# 8_Airframe-Misc.net
KiCad netlist of a schematic drawn in Altium Designer
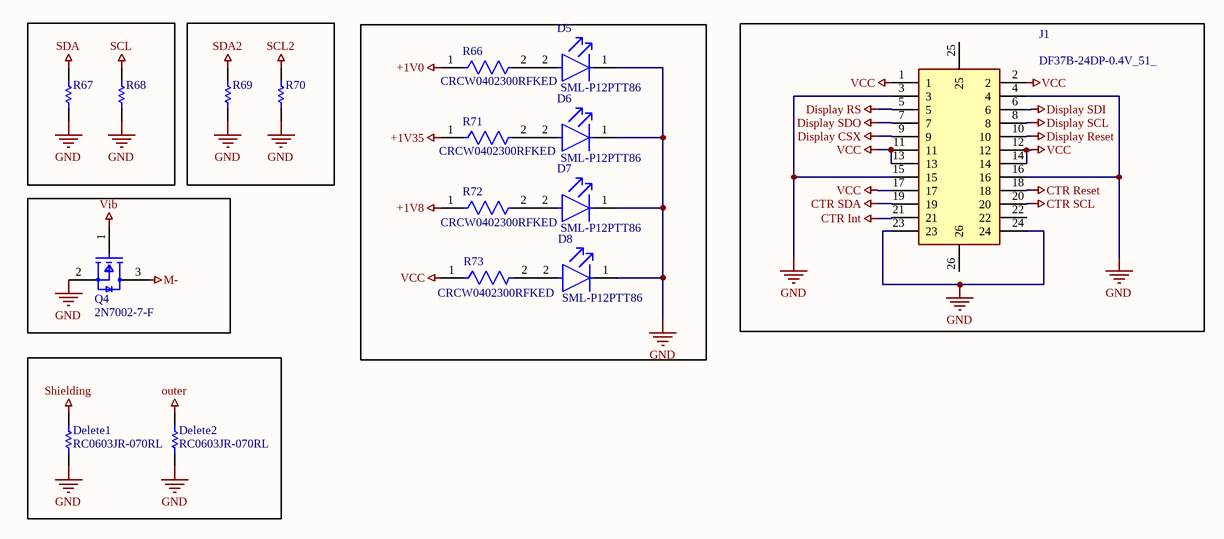
[diagram p0: 8_Airframe-Misc.SchDoc]

(export (version "E")
  (design (tool "Eeschema 10.0.6"))
  (components
    (comp (ref "D5")
      (value "SML-P12PTT86")
      (footprint "FP-SML-P1-MFG")
      (description "LED GREEN CLEAR 1006 SMD")
      (fields
        (field (name "MANUFACTURER") "Rohm")
        (field (name "OCTOPART") "https://octopart.com/sml-p12ptt86-rohm-9290705")
      )
      (libsource (lib "Altium Content Vault") (part "8706943c75ba83719d021d2fdc84c58"))
    )
    (comp (ref "D6")
      (value "SML-P12PTT86")
      (footprint "FP-SML-P1-MFG")
      (description "LED GREEN CLEAR 1006 SMD")
      (fields
        (field (name "MANUFACTURER") "Rohm")
        (field (name "OCTOPART") "https://octopart.com/sml-p12ptt86-rohm-9290705")
      )
      (libsource (lib "Altium Content Vault") (part "8706943c75ba83719d021d2fdc84c58"))
    )
    (comp (ref "D7")
      (value "SML-P12PTT86")
      (footprint "FP-SML-P1-MFG")
      (description "LED GREEN CLEAR 1006 SMD")
      (fields
        (field (name "MANUFACTURER") "Rohm")
        (field (name "OCTOPART") "https://octopart.com/sml-p12ptt86-rohm-9290705")
      )
      (libsource (lib "Altium Content Vault") (part "8706943c75ba83719d021d2fdc84c58"))
    )
    (comp (ref "D8")
      (value "SML-P12PTT86")
      (footprint "FP-SML-P1-MFG")
      (description "LED GREEN CLEAR 1006 SMD")
      (fields
        (field (name "MANUFACTURER") "Rohm")
        (field (name "OCTOPART") "https://octopart.com/sml-p12ptt86-rohm-9290705")
      )
      (libsource (lib "Altium Content Vault") (part "8706943c75ba83719d021d2fdc84c58"))
    )
    (comp (ref "Delete1")
      (value "RC0603JR-070RL")
      (footprint "RESC1608X55X25ML10T15")
      (description "Chip Resistor, 0 Ohm, +/- 5%, 0.1 W, -55 to 155 degC, 0603 (1608 Metric), RoHS, Tape and Reel")
      (fields (field (name "TOLERANCE") "5%") (field (name "MANUFACTURER") "Yageo"))
      (libsource (lib "Altium Content Vault") (part "RES-2"))
    )
    (comp (ref "Delete2")
      (value "RC0603JR-070RL")
      (footprint "RESC1608X55X25ML10T15")
      (description "Chip Resistor, 0 Ohm, +/- 5%, 0.1 W, -55 to 155 degC, 0603 (1608 Metric), RoHS, Tape and Reel")
      (fields (field (name "TOLERANCE") "5%") (field (name "MANUFACTURER") "Yageo"))
      (libsource (lib "Altium Content Vault") (part "RES-2"))
    )
    (comp (ref "J1")
      (value "DF37B-24DP-0.4V_51_")
      (footprint "SamacSys:DF37B24DP04V51")
      (description "Connector")
      (fields
        (field (name "MANUFACTURER_PART_NUMBER") "DF37B-24DP-0.4V(51)")
        (field (name "MOUSER PART NUMBER") "798-DF37B24DP04V51")
      )
      (libsource (lib "*") (part "DF37B-24DP-0.4V_51_"))
    )
    (comp (ref "Q4")
      (value "2N7002-7-F")
      (footprint "FP-SOT23-MFG")
      (description "MOSFET N-CH 60V 115MA SOT23-3")
      (fields (field (name "VOLTAGE") "60V"))
      (libsource (lib "Altium Content Vault") (part "3b9c635fedb024a5347a57b145af9cc"))
    )
    (comp (ref "R66")
      (value "CRCW0402300RFKED")
      (footprint "FP-CRCW0402-e3-MFG")
      (description "RES Thick Film, 300Ω, 1%, 0.063W, 100ppm/°C, 0402")
      (fields (field (name "TOLERANCE") "1%"))
      (libsource (lib "Altium Content Vault") (part "1029c3af85768c4190bb7ad29bc67b5"))
    )
    (comp (ref "R67")
      (value "ERJ-2RKF4701X")
      (footprint "RESC1005X40X25ML05T05")
      (description "Chip Resistor, 4.7 KOhm, +/- 1%, 0.1 W, -55 to 155 degC, 0402 (1005 Metric), RoHS, Tape and Reel")
      (fields (field (name "TOLERANCE") "1%"))
      (libsource (lib "Altium Content Vault") (part "RES-2"))
    )
    (comp (ref "R68")
      (value "ERJ-2RKF4701X")
      (footprint "RESC1005X40X25ML05T05")
      (description "Chip Resistor, 4.7 KOhm, +/- 1%, 0.1 W, -55 to 155 degC, 0402 (1005 Metric), RoHS, Tape and Reel")
      (fields (field (name "TOLERANCE") "1%"))
      (libsource (lib "Altium Content Vault") (part "RES-2"))
    )
    (comp (ref "R69")
      (value "ERJ-2RKF4701X")
      (footprint "RESC1005X40X25ML05T05")
      (description "Chip Resistor, 4.7 KOhm, +/- 1%, 0.1 W, -55 to 155 degC, 0402 (1005 Metric), RoHS, Tape and Reel")
      (fields (field (name "TOLERANCE") "1%"))
      (libsource (lib "Altium Content Vault") (part "RES-2"))
    )
    (comp (ref "R70")
      (value "ERJ-2RKF4701X")
      (footprint "RESC1005X40X25ML05T05")
      (description "Chip Resistor, 4.7 KOhm, +/- 1%, 0.1 W, -55 to 155 degC, 0402 (1005 Metric), RoHS, Tape and Reel")
      (fields (field (name "TOLERANCE") "1%"))
      (libsource (lib "Altium Content Vault") (part "RES-2"))
    )
    (comp (ref "R71")
      (value "CRCW0402300RFKED")
      (footprint "FP-CRCW0402-e3-MFG")
      (description "RES Thick Film, 300Ω, 1%, 0.063W, 100ppm/°C, 0402")
      (fields (field (name "TOLERANCE") "1%"))
      (libsource (lib "Altium Content Vault") (part "1029c3af85768c4190bb7ad29bc67b5"))
    )
    (comp (ref "R72")
      (value "CRCW0402300RFKED")
      (footprint "FP-CRCW0402-e3-MFG")
      (description "RES Thick Film, 300Ω, 1%, 0.063W, 100ppm/°C, 0402")
      (fields (field (name "TOLERANCE") "1%"))
      (libsource (lib "Altium Content Vault") (part "1029c3af85768c4190bb7ad29bc67b5"))
    )
    (comp (ref "R73")
      (value "CRCW0402300RFKED")
      (footprint "FP-CRCW0402-e3-MFG")
      (description "RES Thick Film, 300Ω, 1%, 0.063W, 100ppm/°C, 0402")
      (fields (field (name "TOLERANCE") "1%"))
      (libsource (lib "Altium Content Vault") (part "1029c3af85768c4190bb7ad29bc67b5"))
    )
  )
  (nets
    (net (code "1") (name "+1V0") (class "Default")
      (node (ref "R66") (pin "1") (pinfunction "1_1") (pintype "passive"))
    )
    (net (code "2") (name "+1V8") (class "Default")
      (node (ref "R72") (pin "1") (pinfunction "1_1") (pintype "passive"))
    )
    (net (code "3") (name "+1V35") (class "Default")
      (node (ref "R71") (pin "1") (pinfunction "1_1") (pintype "passive"))
    )
    (net (code "4") (name "CTR Int") (class "Default")
      (node (ref "J1") (pin "21") (pinfunction "21_21") (pintype "passive"))
    )
    (net (code "5") (name "CTR Reset") (class "Default")
      (node (ref "J1") (pin "18") (pinfunction "18_18") (pintype "passive"))
    )
    (net (code "6") (name "CTR SCL") (class "Default")
      (node (ref "J1") (pin "20") (pinfunction "20_20") (pintype "passive"))
    )
    (net (code "7") (name "CTR SDA") (class "Default")
      (node (ref "J1") (pin "19") (pinfunction "19_19") (pintype "passive"))
    )
    (net (code "8") (name "Display CSX") (class "Default")
      (node (ref "J1") (pin "9") (pinfunction "9_9") (pintype "passive"))
    )
    (net (code "9") (name "Display RS") (class "Default")
      (node (ref "J1") (pin "5") (pinfunction "5_5") (pintype "passive"))
    )
    (net (code "10") (name "Display Reset") (class "Default")
      (node (ref "J1") (pin "10") (pinfunction "10_10") (pintype "passive"))
    )
    (net (code "11") (name "Display SCL") (class "Default")
      (node (ref "J1") (pin "8") (pinfunction "8_8") (pintype "passive"))
    )
    (net (code "12") (name "Display SDI") (class "Default")
      (node (ref "J1") (pin "6") (pinfunction "6_6") (pintype "passive"))
    )
    (net (code "13") (name "Display SDO") (class "Default")
      (node (ref "J1") (pin "7") (pinfunction "7_7") (pintype "passive"))
    )
    (net (code "14") (name "GND") (class "Default")
      (node (ref "D5") (pin "1") (pinfunction "C_1") (pintype "passive"))
      (node (ref "D6") (pin "1") (pinfunction "C_1") (pintype "passive"))
      (node (ref "D7") (pin "1") (pinfunction "C_1") (pintype "passive"))
      (node (ref "D8") (pin "1") (pinfunction "C_1") (pintype "passive"))
      (node (ref "Delete1") (pin "1") (pinfunction "1_1") (pintype "passive"))
      (node (ref "Delete2") (pin "1") (pinfunction "1_1") (pintype "passive"))
      (node (ref "J1") (pin "15") (pinfunction "15_15") (pintype "passive"))
      (node (ref "J1") (pin "16") (pinfunction "16_16") (pintype "passive"))
      (node (ref "J1") (pin "23") (pinfunction "23_23") (pintype "passive"))
      (node (ref "J1") (pin "24") (pinfunction "24_24") (pintype "passive"))
      (node (ref "J1") (pin "3") (pinfunction "3_3") (pintype "passive"))
      (node (ref "J1") (pin "4") (pinfunction "4_4") (pintype "passive"))
      (node (ref "Q4") (pin "2") (pinfunction "S_2") (pintype "passive"))
      (node (ref "R67") (pin "1") (pinfunction "1_1") (pintype "passive"))
      (node (ref "R68") (pin "1") (pinfunction "1_1") (pintype "passive"))
      (node (ref "R69") (pin "1") (pinfunction "1_1") (pintype "passive"))
      (node (ref "R70") (pin "1") (pinfunction "1_1") (pintype "passive"))
    )
    (net (code "15") (name "M-") (class "Default")
      (node (ref "Q4") (pin "3") (pinfunction "D_3") (pintype "passive"))
    )
    (net (code "16") (name "Net-(D5-A)") (class "Default")
      (node (ref "D5") (pin "2") (pinfunction "A_2") (pintype "passive"))
      (node (ref "R66") (pin "2") (pinfunction "2_2") (pintype "passive"))
    )
    (net (code "17") (name "Net-(D6-A)") (class "Default")
      (node (ref "D6") (pin "2") (pinfunction "A_2") (pintype "passive"))
      (node (ref "R71") (pin "2") (pinfunction "2_2") (pintype "passive"))
    )
    (net (code "18") (name "Net-(D7-A)") (class "Default")
      (node (ref "D7") (pin "2") (pinfunction "A_2") (pintype "passive"))
      (node (ref "R72") (pin "2") (pinfunction "2_2") (pintype "passive"))
    )
    (net (code "19") (name "Net-(D8-A)") (class "Default")
      (node (ref "D8") (pin "2") (pinfunction "A_2") (pintype "passive"))
      (node (ref "R73") (pin "2") (pinfunction "2_2") (pintype "passive"))
    )
    (net (code "20") (name "SCL") (class "Default")
      (node (ref "R68") (pin "2") (pinfunction "2_2") (pintype "passive"))
    )
    (net (code "21") (name "SCL2") (class "Default")
      (node (ref "R70") (pin "2") (pinfunction "2_2") (pintype "passive"))
    )
    (net (code "22") (name "SDA") (class "Default")
      (node (ref "R67") (pin "2") (pinfunction "2_2") (pintype "passive"))
    )
    (net (code "23") (name "SDA2") (class "Default")
      (node (ref "R69") (pin "2") (pinfunction "2_2") (pintype "passive"))
    )
    (net (code "24") (name "Shielding") (class "Default")
      (node (ref "Delete1") (pin "2") (pinfunction "2_2") (pintype "passive"))
    )
    (net (code "25") (name "VCC") (class "Default")
      (node (ref "J1") (pin "1") (pinfunction "1_1") (pintype "passive"))
      (node (ref "J1") (pin "11") (pinfunction "11_11") (pintype "passive"))
      (node (ref "J1") (pin "12") (pinfunction "12_12") (pintype "passive"))
      (node (ref "J1") (pin "13") (pinfunction "13_13") (pintype "passive"))
      (node (ref "J1") (pin "14") (pinfunction "14_14") (pintype "passive"))
      (node (ref "J1") (pin "17") (pinfunction "17_17") (pintype "passive"))
      (node (ref "J1") (pin "2") (pinfunction "2_2") (pintype "passive"))
      (node (ref "R73") (pin "1") (pinfunction "1_1") (pintype "passive"))
    )
    (net (code "26") (name "Vib") (class "Default")
      (node (ref "Q4") (pin "1") (pinfunction "G_1") (pintype "passive"))
    )
    (net (code "27") (name "outer") (class "Default")
      (node (ref "Delete2") (pin "2") (pinfunction "2_2") (pintype "passive"))
    )
    (net (code "28") (name "unconnected-(J1-Pad22)") (class "Default")
      (node (ref "J1") (pin "22") (pinfunction "22_22") (pintype "passive"))
    )
    (net (code "29") (name "unconnected-(J1-Pad25)") (class "Default")
      (node (ref "J1") (pin "25") (pinfunction "25_25") (pintype "passive"))
    )
    (net (code "30") (name "unconnected-(J1-Pad26)") (class "Default")
      (node (ref "J1") (pin "26") (pinfunction "26_26") (pintype "passive"))
    )
  )
)
